# door_lock.net
KiCad netlist of a schematic drawn in EAGLE
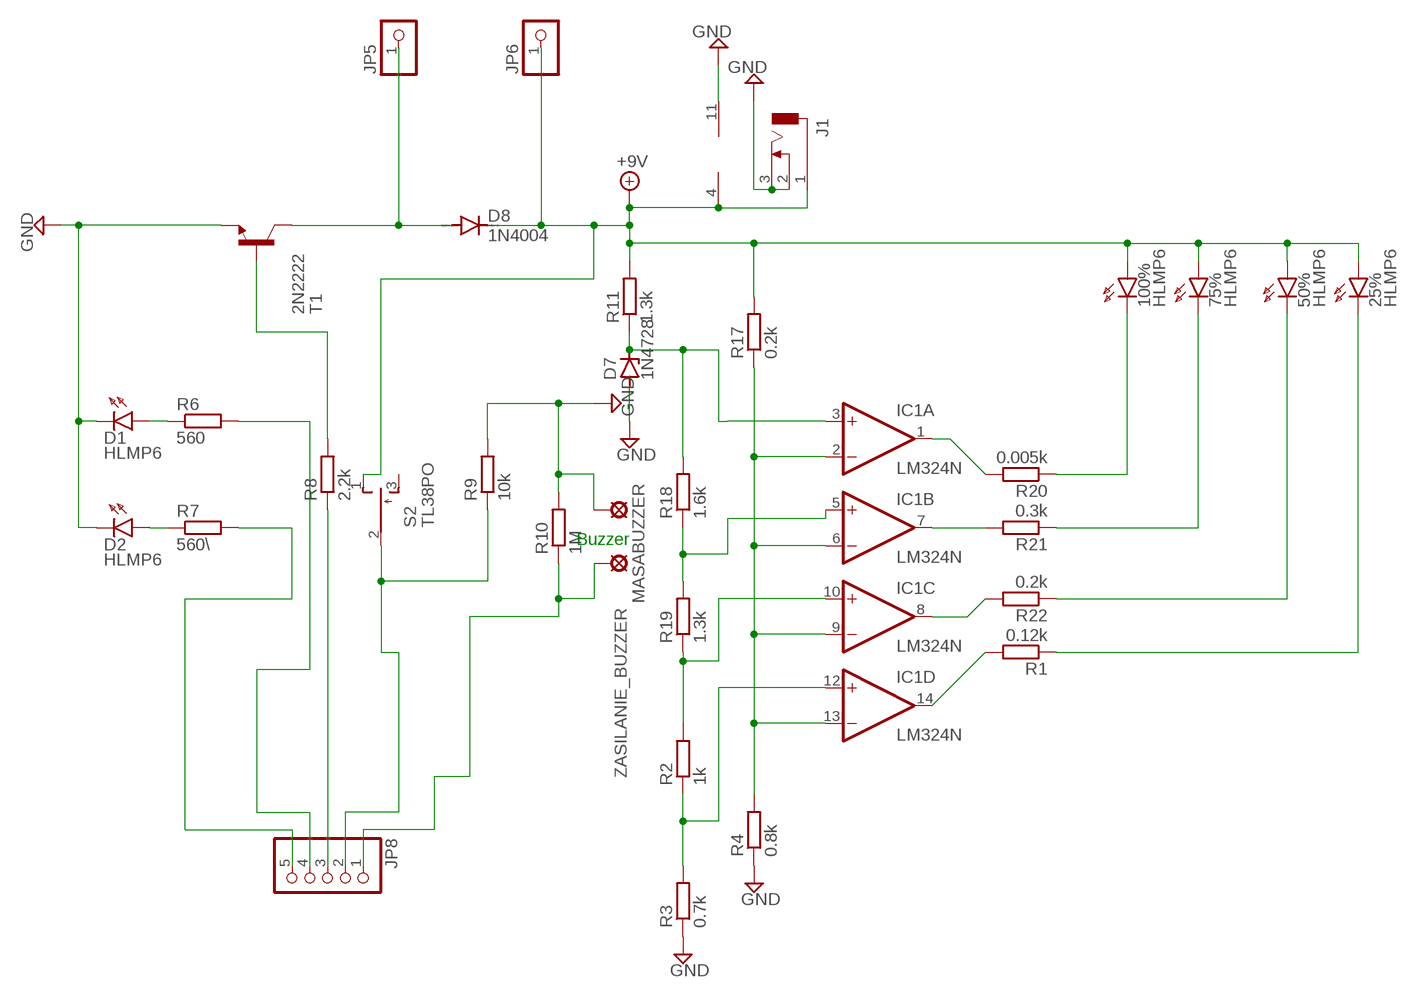
[diagram p0: schematic, sheet 1]

(export (version "E")
  (design (tool "Eeschema 10.0.6"))
  (components
    (comp (ref "25%")
      (value "HLMP6")
      (footprint "eagle-import:HLMP6")
      (fields (field (name "MF") "AGILENT TECHNOLOGIES") (field (name "MPN") "HLMP-6500"))
      (libsource (lib "eagle-import") (part "HLMP6"))
    )
    (comp (ref "50%")
      (value "HLMP6")
      (footprint "eagle-import:HLMP6")
      (fields (field (name "MF") "AGILENT TECHNOLOGIES") (field (name "MPN") "HLMP-6500"))
      (libsource (lib "eagle-import") (part "HLMP6"))
    )
    (comp (ref "75%")
      (value "HLMP6")
      (footprint "eagle-import:HLMP6")
      (fields (field (name "MF") "AGILENT TECHNOLOGIES") (field (name "MPN") "HLMP-6500"))
      (libsource (lib "eagle-import") (part "HLMP6"))
    )
    (comp (ref "100%")
      (value "HLMP6")
      (footprint "eagle-import:HLMP6")
      (fields (field (name "MF") "AGILENT TECHNOLOGIES") (field (name "MPN") "HLMP-6500"))
      (libsource (lib "eagle-import") (part "HLMP6"))
    )
    (comp (ref "D1")
      (value "HLMP6")
      (footprint "eagle-import:HLMP6")
      (fields (field (name "MF") "AGILENT TECHNOLOGIES") (field (name "MPN") "HLMP-6500"))
      (libsource (lib "eagle-import") (part "HLMP6"))
    )
    (comp (ref "D2")
      (value "HLMP6")
      (footprint "eagle-import:HLMP6")
      (fields (field (name "MF") "AGILENT TECHNOLOGIES") (field (name "MPN") "HLMP-6500"))
      (libsource (lib "eagle-import") (part "HLMP6"))
    )
    (comp (ref "D7")
      (value "1N4728")
      (footprint "eagle-import:DO41Z10")
      (libsource (lib "eagle-import") (part "1N4728"))
    )
    (comp (ref "D8")
      (value "1N4004")
      (footprint "eagle-import:DO41-10")
      (libsource (lib "eagle-import") (part "1N4004"))
    )
    (comp (ref "IC1")
      (value "LM324N")
      (footprint "eagle-import:DIL14")
      (libsource (lib "eagle-import") (part "LM324N"))
    )
    (comp (ref "J1")
      (value "DCJ0303")
      (footprint "eagle-import:DCJ0303")
      (libsource (lib "eagle-import") (part "DCJ0303"))
    )
    (comp (ref "JP5")
      (value "PINHD-1X1")
      (footprint "eagle-import:1X01")
      (libsource (lib "eagle-import") (part "PINHD-1X1"))
    )
    (comp (ref "JP6")
      (value "PINHD-1X1")
      (footprint "eagle-import:1X01")
      (libsource (lib "eagle-import") (part "PINHD-1X1"))
    )
    (comp (ref "JP8")
      (value "PINHD-1X5")
      (footprint "eagle-import:1X05")
      (libsource (lib "eagle-import") (part "PINHD-1X5"))
    )
    (comp (ref "MASABUZZER")
      (value "LSP10")
      (footprint "eagle-import:LSP10")
      (libsource (lib "eagle-import") (part "LSP10"))
    )
    (comp (ref "R1")
      (value "0.12k")
      (footprint "eagle-import:0207_10")
      (libsource (lib "eagle-import") (part "R-EU_0207/10"))
    )
    (comp (ref "R2")
      (value "1k")
      (footprint "eagle-import:0207_10")
      (libsource (lib "eagle-import") (part "R-EU_0207/10"))
    )
    (comp (ref "R3")
      (value "0.7k")
      (footprint "eagle-import:0207_10")
      (libsource (lib "eagle-import") (part "R-EU_0207/10"))
    )
    (comp (ref "R4")
      (value "0.8k")
      (footprint "eagle-import:0207_10")
      (libsource (lib "eagle-import") (part "R-EU_0207/10"))
    )
    (comp (ref "R6")
      (value "560")
      (footprint "eagle-import:0207_10")
      (libsource (lib "eagle-import") (part "R-EU_0207/10"))
    )
    (comp (ref "R7")
      (value "560\\")
      (footprint "eagle-import:0207_10")
      (libsource (lib "eagle-import") (part "R-EU_0207/10"))
    )
    (comp (ref "R8")
      (value "2.2k")
      (footprint "eagle-import:0207_10")
      (libsource (lib "eagle-import") (part "R-EU_0207/10"))
    )
    (comp (ref "R9")
      (value "10k")
      (footprint "eagle-import:0207_10")
      (libsource (lib "eagle-import") (part "R-EU_0207/10"))
    )
    (comp (ref "R10")
      (value "1M")
      (footprint "eagle-import:0207_10")
      (libsource (lib "eagle-import") (part "R-EU_0207/10"))
    )
    (comp (ref "R11")
      (value "1.3k")
      (footprint "eagle-import:0207_10")
      (libsource (lib "eagle-import") (part "R-EU_0207/10"))
    )
    (comp (ref "R17")
      (value "0.2k")
      (footprint "eagle-import:0207_10")
      (libsource (lib "eagle-import") (part "R-EU_0207/10"))
    )
    (comp (ref "R18")
      (value "1.6k")
      (footprint "eagle-import:0207_10")
      (libsource (lib "eagle-import") (part "R-EU_0207/10"))
    )
    (comp (ref "R19")
      (value "1.3k")
      (footprint "eagle-import:0207_10")
      (libsource (lib "eagle-import") (part "R-EU_0207/10"))
    )
    (comp (ref "R20")
      (value "0.005k")
      (footprint "eagle-import:0207_10")
      (libsource (lib "eagle-import") (part "R-EU_0207/10"))
    )
    (comp (ref "R21")
      (value "0.3k")
      (footprint "eagle-import:0207_10")
      (libsource (lib "eagle-import") (part "R-EU_0207/10"))
    )
    (comp (ref "R22")
      (value "0.2k")
      (footprint "eagle-import:0207_10")
      (libsource (lib "eagle-import") (part "R-EU_0207/10"))
    )
    (comp (ref "S2")
      (value "TL38PO")
      (footprint "eagle-import:TL3XPO")
      (libsource (lib "eagle-import") (part "TL38PO"))
    )
    (comp (ref "T1")
      (value "2N2222")
      (footprint "eagle-import:TO18")
      (libsource (lib "eagle-import") (part "2N2222"))
    )
    (comp (ref "ZASILANIE_BUZZER")
      (value "LSP10")
      (footprint "eagle-import:LSP10")
      (libsource (lib "eagle-import") (part "LSP10"))
    )
  )
  (nets
    (net (code "1") (name "+9V") (class "Default")
      (node (ref "100%") (pin "A") (pinfunction "A_A") (pintype "passive"))
      (node (ref "25%") (pin "A") (pinfunction "A_A") (pintype "passive"))
      (node (ref "50%") (pin "A") (pinfunction "A_A") (pintype "passive"))
      (node (ref "75%") (pin "A") (pinfunction "A_A") (pintype "passive"))
      (node (ref "D8") (pin "C") (pinfunction "C_C") (pintype "passive"))
      (node (ref "IC1") (pin "4") (pinfunction "V+_4") (pintype "power_in"))
      (node (ref "J1") (pin "1") (pinfunction "1_1") (pintype "passive"))
      (node (ref "JP6") (pin "1") (pinfunction "1_1") (pintype "passive"))
      (node (ref "R11") (pin "2") (pinfunction "2_2") (pintype "passive"))
      (node (ref "R17") (pin "2") (pinfunction "2_2") (pintype "passive"))
      (node (ref "S2") (pin "1") (pinfunction "O_1") (pintype "passive"))
    )
    (net (code "2") (name "GND") (class "Default")
      (node (ref "D1") (pin "K") (pinfunction "K_K") (pintype "passive"))
      (node (ref "D2") (pin "K") (pinfunction "K_K") (pintype "passive"))
      (node (ref "D7") (pin "A") (pinfunction "A_A") (pintype "passive"))
      (node (ref "IC1") (pin "11") (pinfunction "V-_11") (pintype "power_in"))
      (node (ref "J1") (pin "2") (pinfunction "2_2") (pintype "passive"))
      (node (ref "J1") (pin "3") (pinfunction "3_3") (pintype "passive"))
      (node (ref "MASABUZZER") (pin "MP") (pinfunction "MP_MP") (pintype "passive"))
      (node (ref "R10") (pin "2") (pinfunction "2_2") (pintype "passive"))
      (node (ref "R3") (pin "1") (pinfunction "1_1") (pintype "passive"))
      (node (ref "R4") (pin "1") (pinfunction "1_1") (pintype "passive"))
      (node (ref "R9") (pin "2") (pinfunction "2_2") (pintype "passive"))
      (node (ref "T1") (pin "1") (pinfunction "E_1") (pintype "passive"))
    )
    (net (code "3") (name "Net-(25%-PadK)") (class "Default")
      (node (ref "25%") (pin "K") (pinfunction "K_K") (pintype "passive"))
      (node (ref "R1") (pin "1") (pinfunction "1_1") (pintype "passive"))
    )
    (net (code "4") (name "Net-(50%-PadK)") (class "Default")
      (node (ref "50%") (pin "K") (pinfunction "K_K") (pintype "passive"))
      (node (ref "R22") (pin "1") (pinfunction "1_1") (pintype "passive"))
    )
    (net (code "5") (name "Net-(75%-PadK)") (class "Default")
      (node (ref "75%") (pin "K") (pinfunction "K_K") (pintype "passive"))
      (node (ref "R21") (pin "1") (pinfunction "1_1") (pintype "passive"))
    )
    (net (code "6") (name "Net-(100%-PadK)") (class "Default")
      (node (ref "100%") (pin "K") (pinfunction "K_K") (pintype "passive"))
      (node (ref "R20") (pin "1") (pinfunction "1_1") (pintype "passive"))
    )
    (net (code "7") (name "Net-(D1-PadA)") (class "Default")
      (node (ref "D1") (pin "A") (pinfunction "A_A") (pintype "passive"))
      (node (ref "R6") (pin "1") (pinfunction "1_1") (pintype "passive"))
    )
    (net (code "8") (name "Net-(D2-PadA)") (class "Default")
      (node (ref "D2") (pin "A") (pinfunction "A_A") (pintype "passive"))
      (node (ref "R7") (pin "1") (pinfunction "1_1") (pintype "passive"))
    )
    (net (code "9") (name "Net-(IC1A-+IN)") (class "Default")
      (node (ref "D7") (pin "C") (pinfunction "C_C") (pintype "passive"))
      (node (ref "IC1") (pin "3") (pinfunction "+IN_3") (pintype "input"))
      (node (ref "R11") (pin "1") (pinfunction "1_1") (pintype "passive"))
      (node (ref "R18") (pin "2") (pinfunction "2_2") (pintype "passive"))
    )
    (net (code "10") (name "Net-(IC1A--IN)") (class "Default")
      (node (ref "IC1") (pin "13") (pinfunction "-IN_13") (pintype "input"))
      (node (ref "IC1") (pin "2") (pinfunction "-IN_2") (pintype "input"))
      (node (ref "IC1") (pin "6") (pinfunction "-IN_6") (pintype "input"))
      (node (ref "IC1") (pin "9") (pinfunction "-IN_9") (pintype "input"))
      (node (ref "R17") (pin "1") (pinfunction "1_1") (pintype "passive"))
      (node (ref "R4") (pin "2") (pinfunction "2_2") (pintype "passive"))
    )
    (net (code "11") (name "Net-(IC1A-OUT)") (class "Default")
      (node (ref "IC1") (pin "1") (pinfunction "OUT_1") (pintype "output"))
      (node (ref "R20") (pin "2") (pinfunction "2_2") (pintype "passive"))
    )
    (net (code "12") (name "Net-(IC1B-+IN)") (class "Default")
      (node (ref "IC1") (pin "5") (pinfunction "+IN_5") (pintype "input"))
      (node (ref "R18") (pin "1") (pinfunction "1_1") (pintype "passive"))
      (node (ref "R19") (pin "2") (pinfunction "2_2") (pintype "passive"))
    )
    (net (code "13") (name "Net-(IC1B-OUT)") (class "Default")
      (node (ref "IC1") (pin "7") (pinfunction "OUT_7") (pintype "output"))
      (node (ref "R21") (pin "2") (pinfunction "2_2") (pintype "passive"))
    )
    (net (code "14") (name "Net-(IC1C-+IN)") (class "Default")
      (node (ref "IC1") (pin "10") (pinfunction "+IN_10") (pintype "input"))
      (node (ref "R19") (pin "1") (pinfunction "1_1") (pintype "passive"))
      (node (ref "R2") (pin "2") (pinfunction "2_2") (pintype "passive"))
    )
    (net (code "15") (name "Net-(IC1C-OUT)") (class "Default")
      (node (ref "IC1") (pin "8") (pinfunction "OUT_8") (pintype "output"))
      (node (ref "R22") (pin "2") (pinfunction "2_2") (pintype "passive"))
    )
    (net (code "16") (name "Net-(IC1D-+IN)") (class "Default")
      (node (ref "IC1") (pin "12") (pinfunction "+IN_12") (pintype "input"))
      (node (ref "R2") (pin "1") (pinfunction "1_1") (pintype "passive"))
      (node (ref "R3") (pin "2") (pinfunction "2_2") (pintype "passive"))
    )
    (net (code "17") (name "Net-(IC1D-OUT)") (class "Default")
      (node (ref "IC1") (pin "14") (pinfunction "OUT_14") (pintype "output"))
      (node (ref "R1") (pin "2") (pinfunction "2_2") (pintype "passive"))
    )
    (net (code "18") (name "Net-(JP8-Pad1)") (class "Default")
      (node (ref "JP8") (pin "1") (pinfunction "1_1") (pintype "passive"))
      (node (ref "R10") (pin "1") (pinfunction "1_1") (pintype "passive"))
      (node (ref "ZASILANIE_BUZZER") (pin "MP") (pinfunction "MP_MP") (pintype "passive"))
    )
    (net (code "19") (name "Net-(JP8-Pad3)") (class "Default")
      (node (ref "JP8") (pin "3") (pinfunction "3_3") (pintype "passive"))
      (node (ref "R8") (pin "1") (pinfunction "1_1") (pintype "passive"))
    )
    (net (code "20") (name "Net-(JP8-Pad4)") (class "Default")
      (node (ref "JP8") (pin "4") (pinfunction "4_4") (pintype "passive"))
      (node (ref "R6") (pin "2") (pinfunction "2_2") (pintype "passive"))
    )
    (net (code "21") (name "Net-(JP8-Pad5)") (class "Default")
      (node (ref "JP8") (pin "5") (pinfunction "5_5") (pintype "passive"))
      (node (ref "R7") (pin "2") (pinfunction "2_2") (pintype "passive"))
    )
    (net (code "22") (name "Net-(S2-P)") (class "Default")
      (node (ref "JP8") (pin "2") (pinfunction "2_2") (pintype "passive"))
      (node (ref "R9") (pin "1") (pinfunction "1_1") (pintype "passive"))
      (node (ref "S2") (pin "2") (pinfunction "P_2") (pintype "passive"))
    )
    (net (code "23") (name "Net-(T1-B)") (class "Default")
      (node (ref "R8") (pin "2") (pinfunction "2_2") (pintype "passive"))
      (node (ref "T1") (pin "2") (pinfunction "B_2") (pintype "passive"))
    )
    (net (code "24") (name "Net-(T1-C)") (class "Default")
      (node (ref "D8") (pin "A") (pinfunction "A_A") (pintype "passive"))
      (node (ref "JP5") (pin "1") (pinfunction "1_1") (pintype "passive"))
      (node (ref "T1") (pin "3") (pinfunction "C_3") (pintype "passive"))
    )
    (net (code "25") (name "unconnected-(S2-S-Pad3)") (class "Default")
      (node (ref "S2") (pin "3") (pinfunction "S_3") (pintype "passive"))
    )
  )
)
